# ADC108S022_PINOUT.net
KiCad netlist of a schematic drawn in Altium Designer
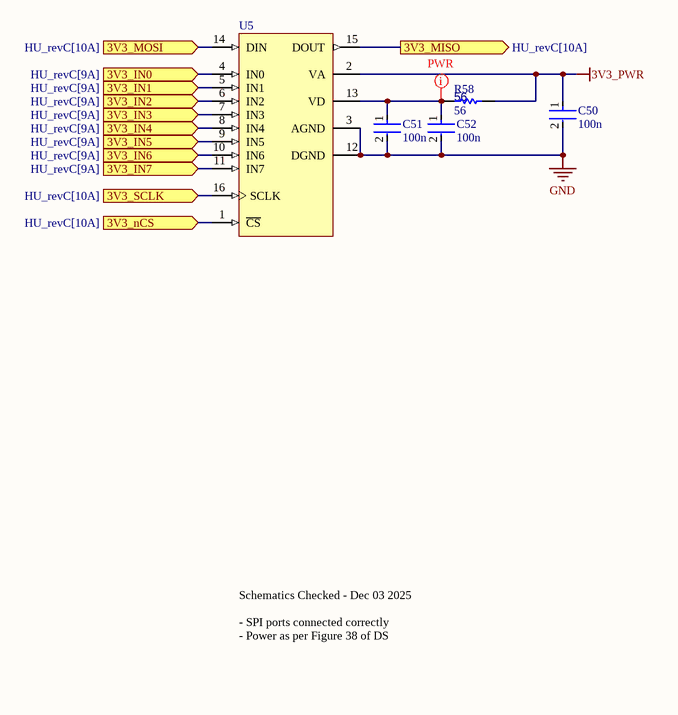
[diagram p0: ADC108S022_PINOUT.SchDoc]

(export (version "E")
  (design (tool "Eeschema 10.0.6"))
  (components
    (comp (ref "C50")
      (value "100n")
      (footprint "FP-0402-L_1_0_0_05-W_0_5-IPC_A")
      (description "LARGE PADS, 0402 CAP, CHANGE COMMENT TO MATCH REAL P/N")
      (libsource (lib "Space Concordia") (part "b4654b650e69147ec39a6b967a45e02"))
    )
    (comp (ref "C51")
      (value "100n")
      (footprint "FP-0402-L_1_0_0_05-W_0_5-IPC_A")
      (description "LARGE PADS, 0402 CAP, CHANGE COMMENT TO MATCH REAL P/N")
      (libsource (lib "Space Concordia") (part "b4654b650e69147ec39a6b967a45e02"))
    )
    (comp (ref "C52")
      (value "100n")
      (footprint "FP-0402-L_1_0_0_05-W_0_5-IPC_A")
      (description "LARGE PADS, 0402 CAP, CHANGE COMMENT TO MATCH REAL P/N")
      (libsource (lib "Space Concordia") (part "b4654b650e69147ec39a6b967a45e02"))
    )
    (comp (ref "R58")
      (value "56")
      (footprint "R0603B")
      (description "Resistor")
      (fields (field (name "ALTIUM_VALUE") "56"))
      (libsource (lib "Space Concordia") (part "Resistor"))
    )
    (comp (ref "U5")
      (value "~")
      (footprint "MTC16_L")
      (description "8-Channel, 50 kSPS to 200 kSPS, 8-Bit A/D Converter, 16-pin TSSOP, Pb-Free")
      (fields (field (name "MANUFACTURER") "National Semiconductor"))
      (libsource (lib "Altium Content Vault") (part "CON-ADC-ADC108S052CIMT"))
    )
  )
  (nets
    (net (code "1") (name "/3V3_IN0") (class "Default")
      (node (ref "U5") (pin "4") (pinfunction "IN0_4") (pintype "input"))
    )
    (net (code "2") (name "/3V3_IN1") (class "Default")
      (node (ref "U5") (pin "5") (pinfunction "IN1_5") (pintype "input"))
    )
    (net (code "3") (name "/3V3_IN2") (class "Default")
      (node (ref "U5") (pin "6") (pinfunction "IN2_6") (pintype "input"))
    )
    (net (code "4") (name "/3V3_IN3") (class "Default")
      (node (ref "U5") (pin "7") (pinfunction "IN3_7") (pintype "input"))
    )
    (net (code "5") (name "/3V3_IN4") (class "Default")
      (node (ref "U5") (pin "8") (pinfunction "IN4_8") (pintype "input"))
    )
    (net (code "6") (name "/3V3_IN5") (class "Default")
      (node (ref "U5") (pin "9") (pinfunction "IN5_9") (pintype "input"))
    )
    (net (code "7") (name "/3V3_IN6") (class "Default")
      (node (ref "U5") (pin "10") (pinfunction "IN6_10") (pintype "input"))
    )
    (net (code "8") (name "/3V3_IN7") (class "Default")
      (node (ref "U5") (pin "11") (pinfunction "IN7_11") (pintype "input"))
    )
    (net (code "9") (name "/3V3_MISO") (class "Default")
      (node (ref "U5") (pin "15") (pinfunction "DOUT_15") (pintype "output"))
    )
    (net (code "10") (name "/3V3_MOSI") (class "Default")
      (node (ref "U5") (pin "14") (pinfunction "DIN_14") (pintype "input"))
    )
    (net (code "11") (name "/3V3_SCLK") (class "Default")
      (node (ref "U5") (pin "16") (pinfunction "SCLK_16") (pintype "input"))
    )
    (net (code "12") (name "/3V3_nCS") (class "Default")
      (node (ref "U5") (pin "1") (pinfunction "~{CS}_1") (pintype "input"))
    )
    (net (code "13") (name "3V3_PWR") (class "Default")
      (node (ref "C50") (pin "1") (pinfunction "1_1") (pintype "passive"))
      (node (ref "R58") (pin "1") (pinfunction "1_1") (pintype "passive"))
      (node (ref "U5") (pin "2") (pinfunction "VA_2") (pintype "power_in"))
    )
    (net (code "14") (name "GND") (class "Default")
      (node (ref "C50") (pin "2") (pinfunction "2_2") (pintype "passive"))
      (node (ref "C51") (pin "2") (pinfunction "2_2") (pintype "passive"))
      (node (ref "C52") (pin "2") (pinfunction "2_2") (pintype "passive"))
      (node (ref "U5") (pin "12") (pinfunction "DGND_12") (pintype "power_in"))
      (node (ref "U5") (pin "3") (pinfunction "AGND_3") (pintype "power_in"))
    )
    (net (code "15") (name "Net-(U5-VD)") (class "Default")
      (node (ref "C51") (pin "1") (pinfunction "1_1") (pintype "passive"))
      (node (ref "C52") (pin "1") (pinfunction "1_1") (pintype "passive"))
      (node (ref "R58") (pin "2") (pinfunction "2_2") (pintype "passive"))
      (node (ref "U5") (pin "13") (pinfunction "VD_13") (pintype "power_in"))
    )
  )
)
